# dwm1000_breakout.net
KiCad netlist of a schematic drawn in EAGLE
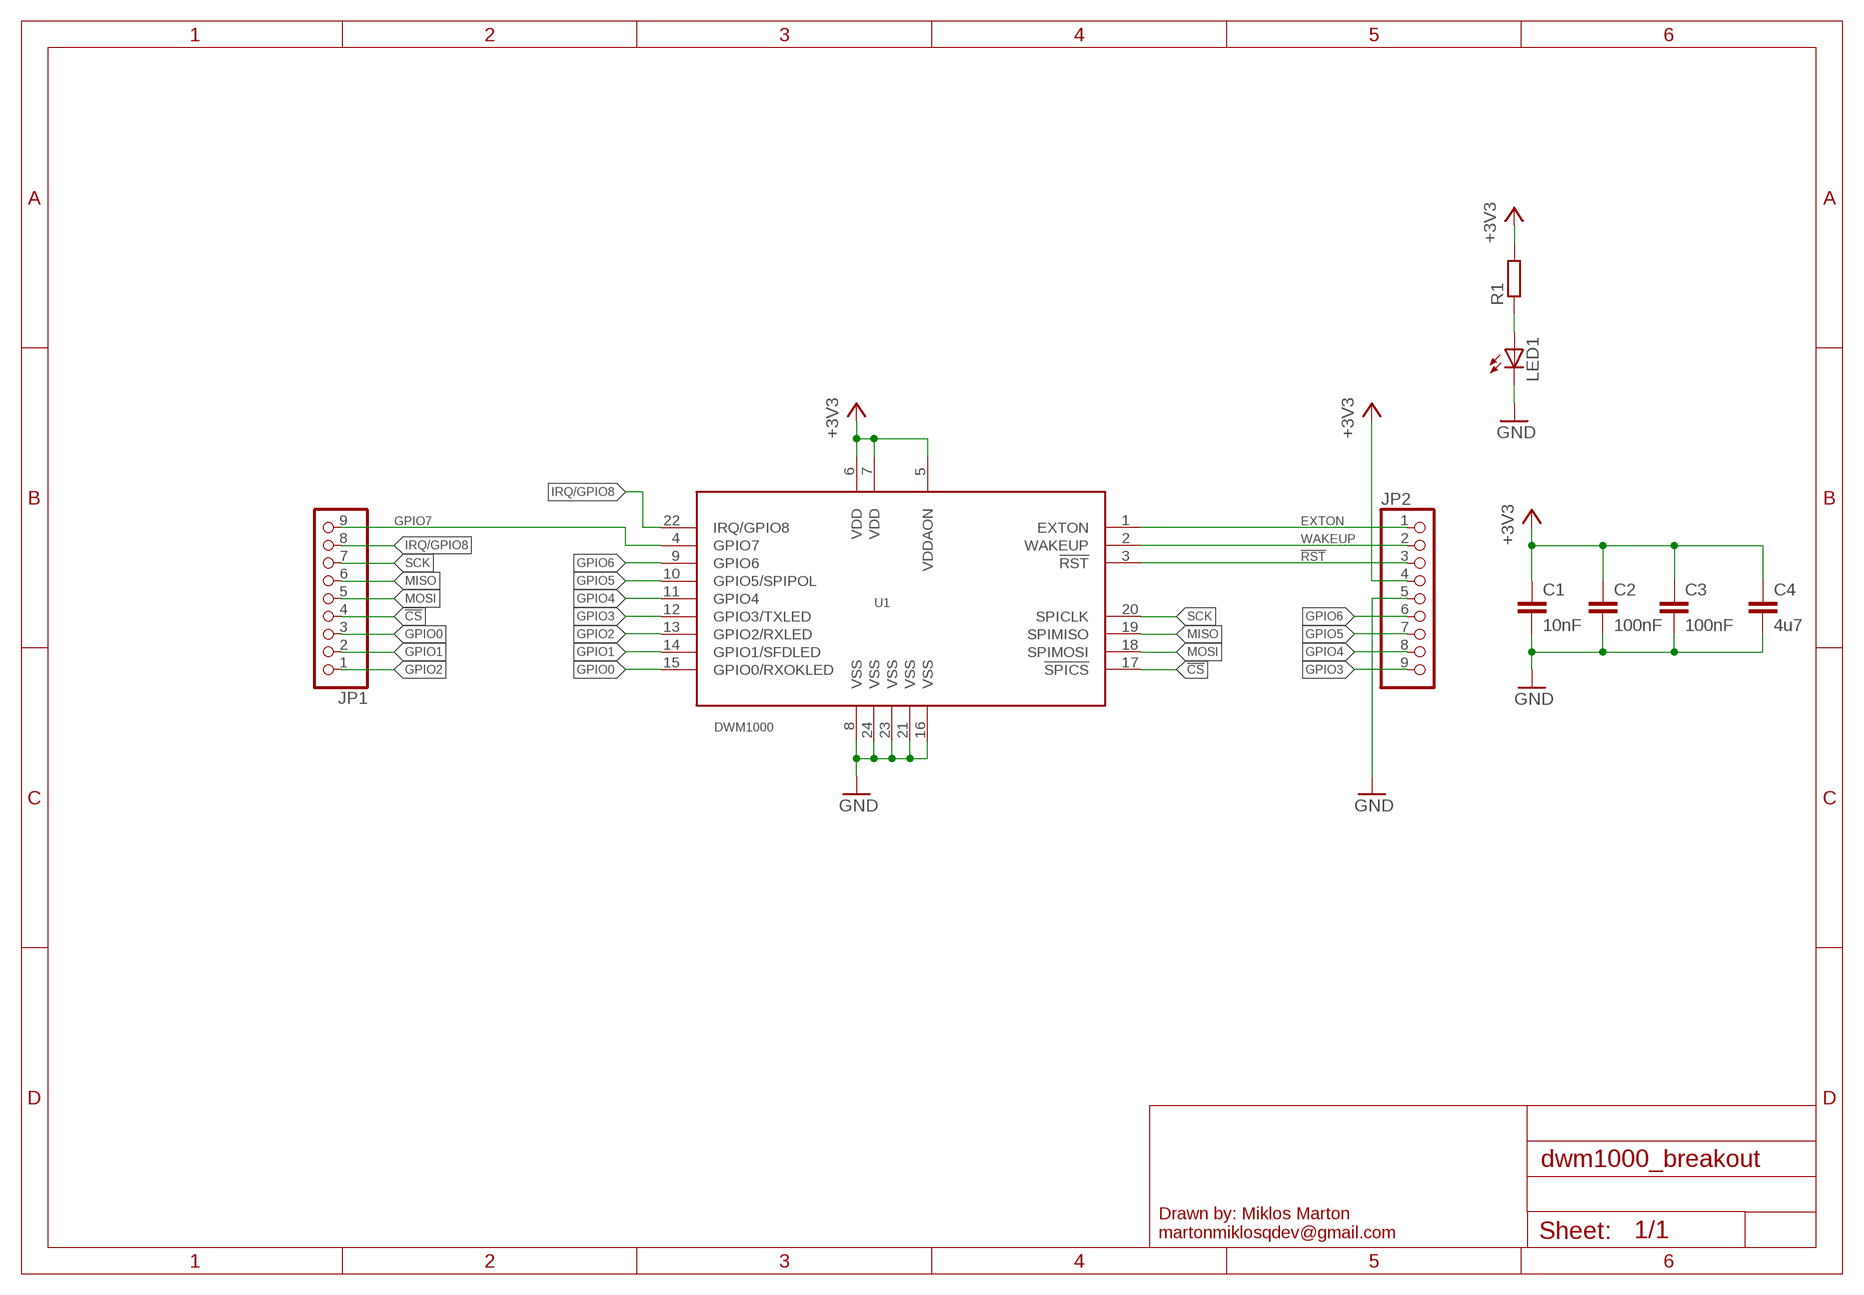
[diagram p0: schematic, sheet 1]

(export (version "E")
  (design (tool "Eeschema 10.0.6"))
  (components
    (comp (ref "C1")
      (value "10nF")
      (footprint "eagle-import:C0603")
      (libsource (lib "eagle-import") (part "C-EUC0603"))
    )
    (comp (ref "C2")
      (value "100nF")
      (footprint "eagle-import:C0603")
      (libsource (lib "eagle-import") (part "C-EUC0603"))
    )
    (comp (ref "C3")
      (value "100nF")
      (footprint "eagle-import:C0603")
      (libsource (lib "eagle-import") (part "C-EUC0603"))
    )
    (comp (ref "C4")
      (value "4u7")
      (footprint "eagle-import:C0805K")
      (libsource (lib "eagle-import") (part "C-EUC0805K"))
    )
    (comp (ref "JP1")
      (value "PINHD-1X9")
      (footprint "eagle-import:1X09")
      (libsource (lib "eagle-import") (part "PINHD-1X9"))
    )
    (comp (ref "JP2")
      (value "PINHD-1X9")
      (footprint "eagle-import:1X09")
      (libsource (lib "eagle-import") (part "PINHD-1X9"))
    )
    (comp (ref "LED1")
      (value "LEDCHIP-LED0603")
      (footprint "eagle-import:CHIP-LED0603")
      (libsource (lib "eagle-import") (part "LEDCHIP-LED0603"))
    )
    (comp (ref "R1")
      (value "R-EU_R0603")
      (footprint "eagle-import:R0603")
      (libsource (lib "eagle-import") (part "R-EU_R0603"))
    )
    (comp (ref "U1")
      (value "DWM1000")
      (footprint "eagle-import:DWM1000")
      (libsource (lib "eagle-import") (part "DWM1000"))
    )
  )
  (nets
    (net (code "1") (name "+3V3") (class "Default")
      (node (ref "C1") (pin "1") (pinfunction "1_1") (pintype "passive"))
      (node (ref "C2") (pin "1") (pinfunction "1_1") (pintype "passive"))
      (node (ref "C3") (pin "1") (pinfunction "1_1") (pintype "passive"))
      (node (ref "C4") (pin "1") (pinfunction "1_1") (pintype "passive"))
      (node (ref "JP2") (pin "4") (pinfunction "4_4") (pintype "passive"))
      (node (ref "R1") (pin "2") (pinfunction "2_2") (pintype "passive"))
      (node (ref "U1") (pin "5") (pinfunction "VDDAON_5") (pintype "bidirectional"))
      (node (ref "U1") (pin "6") (pinfunction "VDD_6") (pintype "passive"))
      (node (ref "U1") (pin "7") (pinfunction "VDD_7") (pintype "passive"))
    )
    (net (code "2") (name "/EXTON") (class "Default")
      (node (ref "JP2") (pin "1") (pinfunction "1_1") (pintype "passive"))
      (node (ref "U1") (pin "1") (pinfunction "EXTON_1") (pintype "output"))
    )
    (net (code "3") (name "/GPIO7") (class "Default")
      (node (ref "JP1") (pin "9") (pinfunction "9_9") (pintype "passive"))
      (node (ref "U1") (pin "4") (pinfunction "GPIO7_4") (pintype "bidirectional"))
    )
    (net (code "4") (name "/WAKEUP") (class "Default")
      (node (ref "JP2") (pin "2") (pinfunction "2_2") (pintype "passive"))
      (node (ref "U1") (pin "2") (pinfunction "WAKEUP_2") (pintype "bidirectional"))
    )
    (net (code "5") (name "/~{CS}") (class "Default")
      (node (ref "JP1") (pin "4") (pinfunction "4_4") (pintype "passive"))
      (node (ref "U1") (pin "17") (pinfunction "~{SPICS}_17") (pintype "input"))
    )
    (net (code "6") (name "/~{RST}") (class "Default")
      (node (ref "JP2") (pin "3") (pinfunction "3_3") (pintype "passive"))
      (node (ref "U1") (pin "3") (pinfunction "~{RST}_3") (pintype "input"))
    )
    (net (code "7") (name "GND") (class "Default")
      (node (ref "C1") (pin "2") (pinfunction "2_2") (pintype "passive"))
      (node (ref "C2") (pin "2") (pinfunction "2_2") (pintype "passive"))
      (node (ref "C3") (pin "2") (pinfunction "2_2") (pintype "passive"))
      (node (ref "C4") (pin "2") (pinfunction "2_2") (pintype "passive"))
      (node (ref "JP2") (pin "5") (pinfunction "5_5") (pintype "passive"))
      (node (ref "LED1") (pin "C") (pinfunction "C_C") (pintype "passive"))
      (node (ref "U1") (pin "16") (pinfunction "VSS_16") (pintype "bidirectional"))
      (node (ref "U1") (pin "21") (pinfunction "VSS_21") (pintype "passive"))
      (node (ref "U1") (pin "23") (pinfunction "VSS_23") (pintype "passive"))
      (node (ref "U1") (pin "24") (pinfunction "VSS_24") (pintype "passive"))
      (node (ref "U1") (pin "8") (pinfunction "VSS_8") (pintype "passive"))
    )
    (net (code "8") (name "GPIO0") (class "Default")
      (node (ref "JP1") (pin "3") (pinfunction "3_3") (pintype "passive"))
      (node (ref "U1") (pin "15") (pinfunction "GPIO0/RXOKLED_15") (pintype "bidirectional"))
    )
    (net (code "9") (name "GPIO1") (class "Default")
      (node (ref "JP1") (pin "2") (pinfunction "2_2") (pintype "passive"))
      (node (ref "U1") (pin "14") (pinfunction "GPIO1/SFDLED_14") (pintype "bidirectional"))
    )
    (net (code "10") (name "GPIO2") (class "Default")
      (node (ref "JP1") (pin "1") (pinfunction "1_1") (pintype "passive"))
      (node (ref "U1") (pin "13") (pinfunction "GPIO2/RXLED_13") (pintype "bidirectional"))
    )
    (net (code "11") (name "GPIO3") (class "Default")
      (node (ref "JP2") (pin "9") (pinfunction "9_9") (pintype "passive"))
      (node (ref "U1") (pin "12") (pinfunction "GPIO3/TXLED_12") (pintype "bidirectional"))
    )
    (net (code "12") (name "GPIO4") (class "Default")
      (node (ref "JP2") (pin "8") (pinfunction "8_8") (pintype "passive"))
      (node (ref "U1") (pin "11") (pinfunction "GPIO4_11") (pintype "bidirectional"))
    )
    (net (code "13") (name "GPIO5") (class "Default")
      (node (ref "JP2") (pin "7") (pinfunction "7_7") (pintype "passive"))
      (node (ref "U1") (pin "10") (pinfunction "GPIO5/SPIPOL_10") (pintype "bidirectional"))
    )
    (net (code "14") (name "GPIO6") (class "Default")
      (node (ref "JP2") (pin "6") (pinfunction "6_6") (pintype "passive"))
      (node (ref "U1") (pin "9") (pinfunction "GPIO6_9") (pintype "bidirectional"))
    )
    (net (code "15") (name "IRQ{slash}GPIO8") (class "Default")
      (node (ref "JP1") (pin "8") (pinfunction "8_8") (pintype "passive"))
      (node (ref "U1") (pin "22") (pinfunction "IRQ/GPIO8_22") (pintype "bidirectional"))
    )
    (net (code "16") (name "MISO") (class "Default")
      (node (ref "JP1") (pin "6") (pinfunction "6_6") (pintype "passive"))
      (node (ref "U1") (pin "19") (pinfunction "SPIMISO_19") (pintype "output"))
    )
    (net (code "17") (name "MOSI") (class "Default")
      (node (ref "JP1") (pin "5") (pinfunction "5_5") (pintype "passive"))
      (node (ref "U1") (pin "18") (pinfunction "SPIMOSI_18") (pintype "input"))
    )
    (net (code "18") (name "Net-(LED1-PadA)") (class "Default")
      (node (ref "LED1") (pin "A") (pinfunction "A_A") (pintype "passive"))
      (node (ref "R1") (pin "1") (pinfunction "1_1") (pintype "passive"))
    )
    (net (code "19") (name "SCK") (class "Default")
      (node (ref "JP1") (pin "7") (pinfunction "7_7") (pintype "passive"))
      (node (ref "U1") (pin "20") (pinfunction "SPICLK_20") (pintype "input"))
    )
  )
)
